# batt_swap.net
KiCad netlist of a schematic drawn in Altium Designer
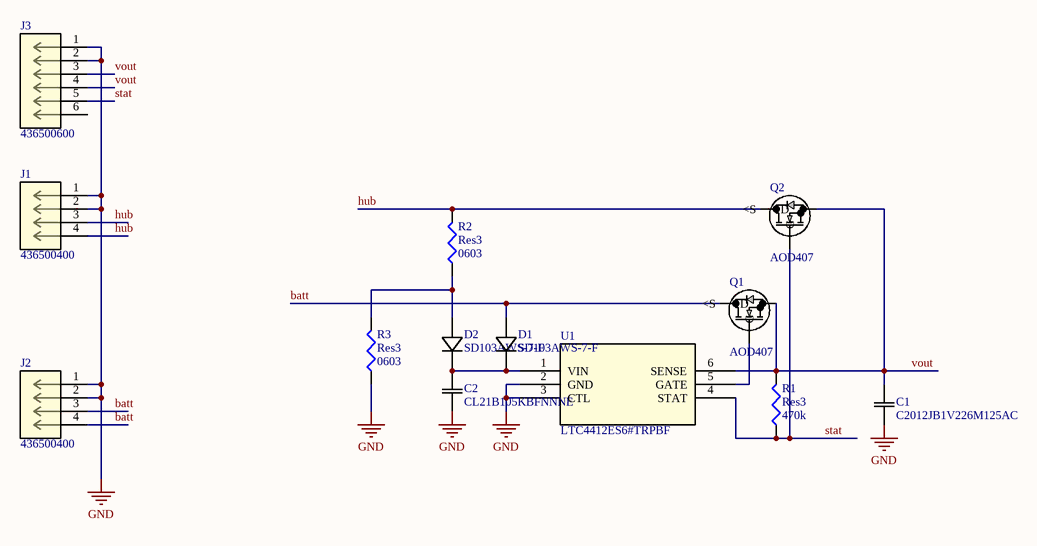
[diagram p0: batt_swap.SchDoc]

(export (version "E")
  (design (tool "Eeschema 10.0.6"))
  (components
    (comp (ref "C1")
      (value "C2012JB1V226M125AC")
      (footprint "swarm_crawler_pcb:CAP_2012_TDK")
      (description "No Description Available")
      (libsource (lib "swarm_crawler_sch") (part "C2012JB1V226M125AC"))
    )
    (comp (ref "C2")
      (value "CL21B105KBFNNNE")
      (footprint "CAP_CL21_SAM")
      (description "No Description Available")
      (libsource (lib "swarm_crawler_sch") (part "CL21B105KBFNNNE"))
    )
    (comp (ref "D1")
      (value "SD103AWS-7-F")
      (footprint "SOD323_DIO")
      (description "No Description Available")
      (libsource (lib "swarm_crawler_sch") (part "SD103AWS-7-F"))
    )
    (comp (ref "D2")
      (value "SD103AWS-7-F")
      (footprint "SOD323_DIO")
      (description "No Description Available")
      (libsource (lib "swarm_crawler_sch") (part "SD103AWS-7-F"))
    )
    (comp (ref "J1")
      (value "436500400")
      (footprint "swarm_crawler_pcb:CON_436500400_MOL")
      (description "No Description Available")
      (fields (field (name "COPYRIGHT") "Copyright (C) 2023 Ultra Librarian. All rights reserved."))
      (libsource (lib "swarm_crawler_sch") (part "436500400"))
    )
    (comp (ref "J2")
      (value "436500400")
      (footprint "swarm_crawler_pcb:CON_436500400_MOL")
      (description "No Description Available")
      (fields (field (name "COPYRIGHT") "Copyright (C) 2023 Ultra Librarian. All rights reserved."))
      (libsource (lib "swarm_crawler_sch") (part "436500400"))
    )
    (comp (ref "J3")
      (value "436500600")
      (footprint "swarm_crawler_pcb:CON_436500600_MOL")
      (description "No Description Available")
      (fields (field (name "COPYRIGHT") "Copyright (C) 2023 Ultra Librarian. All rights reserved."))
      (libsource (lib "swarm_crawler_sch") (part "436500600"))
    )
    (comp (ref "Q1")
      (value "AOD407")
      (footprint "TO252_AOS")
      (description "No Description Available")
      (fields
        (field (name "MANUFACTURER_PART_NUMBER") "AOD256")
        (field (name "COPYRIGHT") "Copyright (C) 2023 Ultra Librarian. All rights reserved.")
      )
      (libsource (lib "swarm_crawler_sch") (part "AOD407"))
    )
    (comp (ref "Q2")
      (value "AOD407")
      (footprint "TO252_AOS")
      (description "No Description Available")
      (fields
        (field (name "MANUFACTURER_PART_NUMBER") "AOD256")
        (field (name "COPYRIGHT") "Copyright (C) 2023 Ultra Librarian. All rights reserved.")
      )
      (libsource (lib "swarm_crawler_sch") (part "AOD407"))
    )
    (comp (ref "R1")
      (value "Res3")
      (footprint "J1-0603")
      (description "Resistor")
      (fields (field (name "ALTIUM_VALUE") "470k") (field (name "PUBLISHER") "Altium Limited"))
      (libsource (lib "Miscellaneous Devices") (part "Res3"))
    )
    (comp (ref "R2")
      (value "Res3")
      (footprint "J1-0603")
      (description "Resistor")
      (fields (field (name "ALTIUM_VALUE") "0603") (field (name "PUBLISHER") "Altium Limited"))
      (libsource (lib "Miscellaneous Devices") (part "Res3"))
    )
    (comp (ref "R3")
      (value "Res3")
      (footprint "J1-0603")
      (description "Resistor")
      (fields (field (name "ALTIUM_VALUE") "0603") (field (name "PUBLISHER") "Altium Limited"))
      (libsource (lib "Miscellaneous Devices") (part "Res3"))
    )
    (comp (ref "U1")
      (value "LTC4412ES6#TRPBF")
      (footprint "LTC4412ES6#TRPBF_ADI")
      (description "No Description Available")
      (libsource (lib "swarm_crawler_sch") (part "LTC4412ES6#TRPBF"))
    )
  )
  (nets
    (net (code "1") (name "/batt") (class "Default")
      (node (ref "D1") (pin "2") (pinfunction "2_2") (pintype "passive"))
      (node (ref "J2") (pin "3") (pinfunction "3_3") (pintype "passive"))
      (node (ref "J2") (pin "4") (pinfunction "4_4") (pintype "passive"))
      (node (ref "Q1") (pin "3") (pinfunction "D_3") (pintype "passive"))
    )
    (net (code "2") (name "/hub") (class "Default")
      (node (ref "J1") (pin "3") (pinfunction "3_3") (pintype "passive"))
      (node (ref "J1") (pin "4") (pinfunction "4_4") (pintype "passive"))
      (node (ref "Q2") (pin "3") (pinfunction "D_3") (pintype "passive"))
      (node (ref "R2") (pin "2") (pinfunction "2_2") (pintype "passive"))
    )
    (net (code "3") (name "/stat") (class "Default")
      (node (ref "J3") (pin "5") (pinfunction "5_5") (pintype "passive"))
      (node (ref "Q2") (pin "1") (pinfunction "G_1") (pintype "passive"))
      (node (ref "R1") (pin "1") (pinfunction "1_1") (pintype "passive"))
      (node (ref "U1") (pin "4") (pinfunction "STAT_4") (pintype "passive"))
    )
    (net (code "4") (name "/vout") (class "Default")
      (node (ref "C1") (pin "2") (pinfunction "2_2") (pintype "passive"))
      (node (ref "J3") (pin "3") (pinfunction "3_3") (pintype "passive"))
      (node (ref "J3") (pin "4") (pinfunction "4_4") (pintype "passive"))
      (node (ref "Q1") (pin "2") (pinfunction "<S_2") (pintype "passive"))
      (node (ref "Q2") (pin "2") (pinfunction "<S_2") (pintype "passive"))
      (node (ref "R1") (pin "2") (pinfunction "2_2") (pintype "passive"))
      (node (ref "U1") (pin "6") (pinfunction "SENSE_6") (pintype "passive"))
    )
    (net (code "5") (name "GND") (class "Default")
      (node (ref "C1") (pin "1") (pinfunction "1_1") (pintype "passive"))
      (node (ref "C2") (pin "1") (pinfunction "1_1") (pintype "passive"))
      (node (ref "J1") (pin "1") (pinfunction "1_1") (pintype "passive"))
      (node (ref "J1") (pin "2") (pinfunction "2_2") (pintype "passive"))
      (node (ref "J2") (pin "1") (pinfunction "1_1") (pintype "passive"))
      (node (ref "J2") (pin "2") (pinfunction "2_2") (pintype "passive"))
      (node (ref "J3") (pin "1") (pinfunction "1_1") (pintype "passive"))
      (node (ref "J3") (pin "2") (pinfunction "2_2") (pintype "passive"))
      (node (ref "R3") (pin "1") (pinfunction "1_1") (pintype "passive"))
      (node (ref "U1") (pin "2") (pinfunction "GND_2") (pintype "passive"))
      (node (ref "U1") (pin "3") (pinfunction "CTL_3") (pintype "passive"))
    )
    (net (code "6") (name "Net-(D2-Pad2)") (class "Default")
      (node (ref "D2") (pin "2") (pinfunction "2_2") (pintype "passive"))
      (node (ref "R2") (pin "1") (pinfunction "1_1") (pintype "passive"))
      (node (ref "R3") (pin "2") (pinfunction "2_2") (pintype "passive"))
    )
    (net (code "7") (name "Net-(Q1-G)") (class "Default")
      (node (ref "Q1") (pin "1") (pinfunction "G_1") (pintype "passive"))
      (node (ref "U1") (pin "5") (pinfunction "GATE_5") (pintype "passive"))
    )
    (net (code "8") (name "Net-(U1-VIN)") (class "Default")
      (node (ref "C2") (pin "2") (pinfunction "2_2") (pintype "passive"))
      (node (ref "D1") (pin "1") (pinfunction "1_1") (pintype "passive"))
      (node (ref "D2") (pin "1") (pinfunction "1_1") (pintype "passive"))
      (node (ref "U1") (pin "1") (pinfunction "VIN_1") (pintype "passive"))
    )
    (net (code "9") (name "unconnected-(J3-Pad6)") (class "Default")
      (node (ref "J3") (pin "6") (pinfunction "6_6") (pintype "passive"))
    )
  )
)
